# ringled.net
KiCad netlist of a schematic drawn in Altium Designer
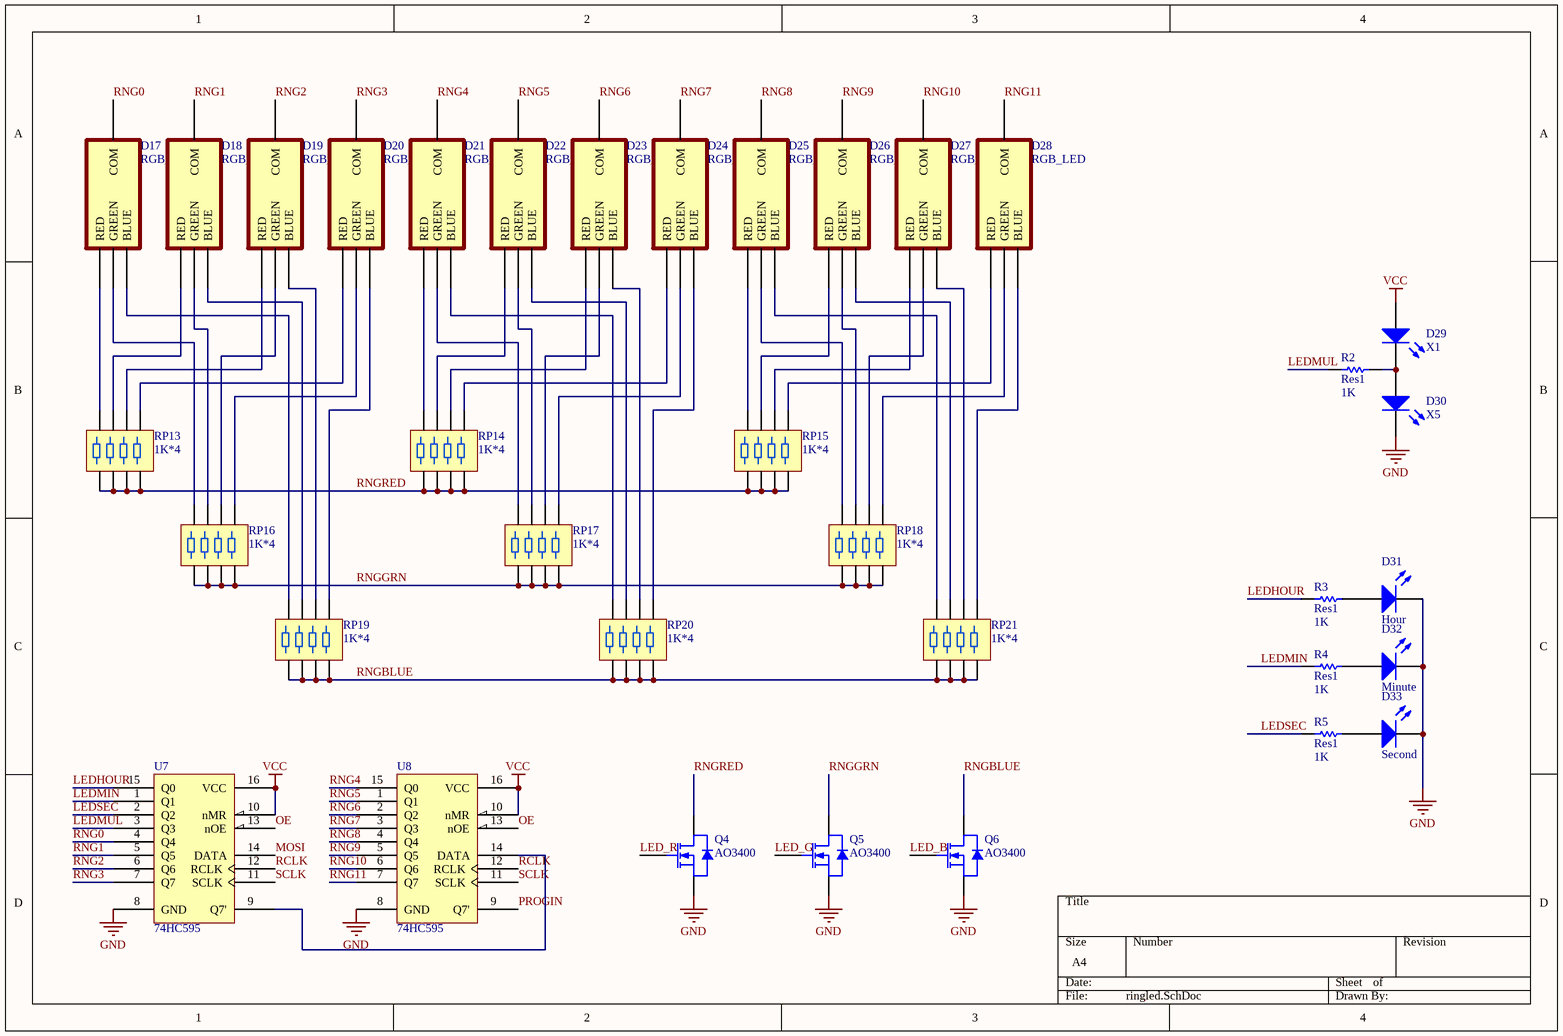
[diagram p0: ringled.SchDoc]

(export (version "E")
  (design (tool "Eeschema 10.0.6"))
  (components
    (comp (ref "D17")
      (value "RGB_LED")
      (footprint "0805_RGB")
      (libsource (lib "ntw_oldschlib") (part "RGBLED"))
    )
    (comp (ref "D18")
      (value "RGB_LED")
      (footprint "0805_RGB")
      (libsource (lib "ntw_oldschlib") (part "RGBLED"))
    )
    (comp (ref "D19")
      (value "RGB_LED")
      (footprint "0805_RGB")
      (libsource (lib "ntw_oldschlib") (part "RGBLED"))
    )
    (comp (ref "D20")
      (value "RGB_LED")
      (footprint "0805_RGB")
      (libsource (lib "ntw_oldschlib") (part "RGBLED"))
    )
    (comp (ref "D21")
      (value "RGB_LED")
      (footprint "0805_RGB")
      (libsource (lib "ntw_oldschlib") (part "RGBLED"))
    )
    (comp (ref "D22")
      (value "RGB_LED")
      (footprint "0805_RGB")
      (libsource (lib "ntw_oldschlib") (part "RGBLED"))
    )
    (comp (ref "D23")
      (value "RGB_LED")
      (footprint "0805_RGB")
      (libsource (lib "ntw_oldschlib") (part "RGBLED"))
    )
    (comp (ref "D24")
      (value "RGB_LED")
      (footprint "0805_RGB")
      (libsource (lib "ntw_oldschlib") (part "RGBLED"))
    )
    (comp (ref "D25")
      (value "RGB_LED")
      (footprint "0805_RGB")
      (libsource (lib "ntw_oldschlib") (part "RGBLED"))
    )
    (comp (ref "D26")
      (value "RGB_LED")
      (footprint "0805_RGB")
      (libsource (lib "ntw_oldschlib") (part "RGBLED"))
    )
    (comp (ref "D27")
      (value "RGB_LED")
      (footprint "0805_RGB")
      (libsource (lib "ntw_oldschlib") (part "RGBLED"))
    )
    (comp (ref "D28")
      (value "RGB_LED")
      (footprint "0805_RGB")
      (libsource (lib "ntw_oldschlib") (part "RGBLED"))
    )
    (comp (ref "D29")
      (value "X1")
      (footprint "0805_LED")
      (description "Typical INFRARED GaAs LED")
      (fields (field (name "PUBLISHER") "Altium Limited"))
      (libsource (lib "Miscellaneous Devices") (part "LED0"))
    )
    (comp (ref "D30")
      (value "X5")
      (footprint "0805_LED")
      (description "Typical INFRARED GaAs LED")
      (fields (field (name "PUBLISHER") "Altium Limited"))
      (libsource (lib "Miscellaneous Devices") (part "LED0"))
    )
    (comp (ref "D31")
      (value "Hour")
      (footprint "0805_LED")
      (description "Typical INFRARED GaAs LED")
      (fields (field (name "PUBLISHER") "Altium Limited"))
      (libsource (lib "Miscellaneous Devices") (part "LED0"))
    )
    (comp (ref "D32")
      (value "Minute")
      (footprint "0805_LED")
      (description "Typical INFRARED GaAs LED")
      (fields (field (name "PUBLISHER") "Altium Limited"))
      (libsource (lib "Miscellaneous Devices") (part "LED0"))
    )
    (comp (ref "D33")
      (value "Second")
      (footprint "0805_LED")
      (description "Typical INFRARED GaAs LED")
      (fields (field (name "PUBLISHER") "Altium Limited"))
      (libsource (lib "Miscellaneous Devices") (part "LED0"))
    )
    (comp (ref "Q4")
      (value "AO3400")
      (footprint "SOT-23")
      (description "N-Channel MOSFET")
      (fields (field (name "PUBLISHER") "Altium Limited"))
      (libsource (lib "ntw_oldschlib") (part "AO3400"))
    )
    (comp (ref "Q5")
      (value "AO3400")
      (footprint "SOT-23")
      (description "N-Channel MOSFET")
      (fields (field (name "PUBLISHER") "Altium Limited"))
      (libsource (lib "ntw_oldschlib") (part "AO3400"))
    )
    (comp (ref "Q6")
      (value "AO3400")
      (footprint "SOT-23")
      (description "N-Channel MOSFET")
      (fields (field (name "PUBLISHER") "Altium Limited"))
      (libsource (lib "ntw_oldschlib") (part "AO3400"))
    )
    (comp (ref "R2")
      (value "Res1")
      (footprint "0805")
      (description "Resistor")
      (fields (field (name "ALTIUM_VALUE") "1K") (field (name "PUBLISHER") "Altium Limited"))
      (libsource (lib "Miscellaneous Devices") (part "Res1"))
    )
    (comp (ref "R3")
      (value "Res1")
      (footprint "0805")
      (description "Resistor")
      (fields (field (name "ALTIUM_VALUE") "1K") (field (name "PUBLISHER") "Altium Limited"))
      (libsource (lib "Miscellaneous Devices") (part "Res1"))
    )
    (comp (ref "R4")
      (value "Res1")
      (footprint "0805")
      (description "Resistor")
      (fields (field (name "ALTIUM_VALUE") "1K") (field (name "PUBLISHER") "Altium Limited"))
      (libsource (lib "Miscellaneous Devices") (part "Res1"))
    )
    (comp (ref "R5")
      (value "Res1")
      (footprint "0805")
      (description "Resistor")
      (fields (field (name "ALTIUM_VALUE") "1K") (field (name "PUBLISHER") "Altium Limited"))
      (libsource (lib "Miscellaneous Devices") (part "Res1"))
    )
    (comp (ref "RP13") (value "1K*4") (footprint "0603X4") (libsource (lib "ntw_oldschlib") (part "RPack_4")))
    (comp (ref "RP14") (value "1K*4") (footprint "0603X4") (libsource (lib "ntw_oldschlib") (part "RPack_4")))
    (comp (ref "RP15") (value "1K*4") (footprint "0603X4") (libsource (lib "ntw_oldschlib") (part "RPack_4")))
    (comp (ref "RP16") (value "1K*4") (footprint "0603X4") (libsource (lib "ntw_oldschlib") (part "RPack_4")))
    (comp (ref "RP17") (value "1K*4") (footprint "0603X4") (libsource (lib "ntw_oldschlib") (part "RPack_4")))
    (comp (ref "RP18") (value "1K*4") (footprint "0603X4") (libsource (lib "ntw_oldschlib") (part "RPack_4")))
    (comp (ref "RP19") (value "1K*4") (footprint "0603X4") (libsource (lib "ntw_oldschlib") (part "RPack_4")))
    (comp (ref "RP20") (value "1K*4") (footprint "0603X4") (libsource (lib "ntw_oldschlib") (part "RPack_4")))
    (comp (ref "RP21") (value "1K*4") (footprint "0603X4") (libsource (lib "ntw_oldschlib") (part "RPack_4")))
    (comp (ref "U7")
      (value "74HC595")
      (footprint "TSSOP16")
      (description "8-bit serial-in, serial or parallel-out shift register with output latches; 3-state")
      (libsource (lib "ntw_oldschlib") (part "74HC595"))
    )
    (comp (ref "U8")
      (value "74HC595")
      (footprint "TSSOP16")
      (description "8-bit serial-in, serial or parallel-out shift register with output latches; 3-state")
      (libsource (lib "ntw_oldschlib") (part "74HC595"))
    )
  )
  (nets
    (net (code "1") (name "/LEDHOUR") (class "Default")
      (node (ref "R3") (pin "1") (pinfunction "1_1") (pintype "passive"))
      (node (ref "U7") (pin "15") (pinfunction "Q0_15") (pintype "passive"))
    )
    (net (code "2") (name "/LEDMIN") (class "Default")
      (node (ref "R4") (pin "1") (pinfunction "1_1") (pintype "passive"))
      (node (ref "U7") (pin "1") (pinfunction "Q1_1") (pintype "passive"))
    )
    (net (code "3") (name "/LEDMUL") (class "Default")
      (node (ref "R2") (pin "1") (pinfunction "1_1") (pintype "passive"))
      (node (ref "U7") (pin "3") (pinfunction "Q3_3") (pintype "passive"))
    )
    (net (code "4") (name "/LEDSEC") (class "Default")
      (node (ref "R5") (pin "1") (pinfunction "1_1") (pintype "passive"))
      (node (ref "U7") (pin "2") (pinfunction "Q2_2") (pintype "passive"))
    )
    (net (code "5") (name "/LED_B") (class "Default")
      (node (ref "Q6") (pin "1") (pinfunction "G_1") (pintype "passive"))
    )
    (net (code "6") (name "/LED_G") (class "Default")
      (node (ref "Q5") (pin "1") (pinfunction "G_1") (pintype "passive"))
    )
    (net (code "7") (name "/LED_R") (class "Default")
      (node (ref "Q4") (pin "1") (pinfunction "G_1") (pintype "passive"))
    )
    (net (code "8") (name "/MOSI") (class "Default")
      (node (ref "U7") (pin "14") (pinfunction "DATA_14") (pintype "passive"))
    )
    (net (code "9") (name "/OE") (class "Default")
      (node (ref "U7") (pin "13") (pinfunction "nOE_13") (pintype "passive"))
      (node (ref "U8") (pin "13") (pinfunction "nOE_13") (pintype "passive"))
    )
    (net (code "10") (name "/PROGIN") (class "Default")
      (node (ref "U8") (pin "9") (pinfunction "Q7'_9") (pintype "passive"))
    )
    (net (code "11") (name "/RCLK") (class "Default")
      (node (ref "U7") (pin "12") (pinfunction "RCLK_12") (pintype "passive"))
      (node (ref "U8") (pin "12") (pinfunction "RCLK_12") (pintype "passive"))
    )
    (net (code "12") (name "/RNG0") (class "Default")
      (node (ref "D17") (pin "COM") (pinfunction "COM_COM") (pintype "passive"))
      (node (ref "U7") (pin "4") (pinfunction "Q4_4") (pintype "passive"))
    )
    (net (code "13") (name "/RNG1") (class "Default")
      (node (ref "D18") (pin "COM") (pinfunction "COM_COM") (pintype "passive"))
      (node (ref "U7") (pin "5") (pinfunction "Q5_5") (pintype "passive"))
    )
    (net (code "14") (name "/RNG2") (class "Default")
      (node (ref "D19") (pin "COM") (pinfunction "COM_COM") (pintype "passive"))
      (node (ref "U7") (pin "6") (pinfunction "Q6_6") (pintype "passive"))
    )
    (net (code "15") (name "/RNG3") (class "Default")
      (node (ref "D20") (pin "COM") (pinfunction "COM_COM") (pintype "passive"))
      (node (ref "U7") (pin "7") (pinfunction "Q7_7") (pintype "passive"))
    )
    (net (code "16") (name "/RNG4") (class "Default")
      (node (ref "D21") (pin "COM") (pinfunction "COM_COM") (pintype "passive"))
      (node (ref "U8") (pin "15") (pinfunction "Q0_15") (pintype "passive"))
    )
    (net (code "17") (name "/RNG5") (class "Default")
      (node (ref "D22") (pin "COM") (pinfunction "COM_COM") (pintype "passive"))
      (node (ref "U8") (pin "1") (pinfunction "Q1_1") (pintype "passive"))
    )
    (net (code "18") (name "/RNG6") (class "Default")
      (node (ref "D23") (pin "COM") (pinfunction "COM_COM") (pintype "passive"))
      (node (ref "U8") (pin "2") (pinfunction "Q2_2") (pintype "passive"))
    )
    (net (code "19") (name "/RNG7") (class "Default")
      (node (ref "D24") (pin "COM") (pinfunction "COM_COM") (pintype "passive"))
      (node (ref "U8") (pin "3") (pinfunction "Q3_3") (pintype "passive"))
    )
    (net (code "20") (name "/RNG8") (class "Default")
      (node (ref "D25") (pin "COM") (pinfunction "COM_COM") (pintype "passive"))
      (node (ref "U8") (pin "4") (pinfunction "Q4_4") (pintype "passive"))
    )
    (net (code "21") (name "/RNG9") (class "Default")
      (node (ref "D26") (pin "COM") (pinfunction "COM_COM") (pintype "passive"))
      (node (ref "U8") (pin "5") (pinfunction "Q5_5") (pintype "passive"))
    )
    (net (code "22") (name "/RNG10") (class "Default")
      (node (ref "D27") (pin "COM") (pinfunction "COM_COM") (pintype "passive"))
      (node (ref "U8") (pin "6") (pinfunction "Q6_6") (pintype "passive"))
    )
    (net (code "23") (name "/RNG11") (class "Default")
      (node (ref "D28") (pin "COM") (pinfunction "COM_COM") (pintype "passive"))
      (node (ref "U8") (pin "7") (pinfunction "Q7_7") (pintype "passive"))
    )
    (net (code "24") (name "/RNGBLUE") (class "Default")
      (node (ref "Q6") (pin "3") (pinfunction "D_3") (pintype "passive"))
      (node (ref "RP19") (pin "1") (pinfunction "1_1") (pintype "passive"))
      (node (ref "RP19") (pin "2") (pinfunction "2_2") (pintype "passive"))
      (node (ref "RP19") (pin "3") (pinfunction "3_3") (pintype "passive"))
      (node (ref "RP19") (pin "4") (pinfunction "4_4") (pintype "passive"))
      (node (ref "RP20") (pin "1") (pinfunction "1_1") (pintype "passive"))
      (node (ref "RP20") (pin "2") (pinfunction "2_2") (pintype "passive"))
      (node (ref "RP20") (pin "3") (pinfunction "3_3") (pintype "passive"))
      (node (ref "RP20") (pin "4") (pinfunction "4_4") (pintype "passive"))
      (node (ref "RP21") (pin "1") (pinfunction "1_1") (pintype "passive"))
      (node (ref "RP21") (pin "2") (pinfunction "2_2") (pintype "passive"))
      (node (ref "RP21") (pin "3") (pinfunction "3_3") (pintype "passive"))
      (node (ref "RP21") (pin "4") (pinfunction "4_4") (pintype "passive"))
    )
    (net (code "25") (name "/RNGGRN") (class "Default")
      (node (ref "Q5") (pin "3") (pinfunction "D_3") (pintype "passive"))
      (node (ref "RP16") (pin "1") (pinfunction "1_1") (pintype "passive"))
      (node (ref "RP16") (pin "2") (pinfunction "2_2") (pintype "passive"))
      (node (ref "RP16") (pin "3") (pinfunction "3_3") (pintype "passive"))
      (node (ref "RP16") (pin "4") (pinfunction "4_4") (pintype "passive"))
      (node (ref "RP17") (pin "1") (pinfunction "1_1") (pintype "passive"))
      (node (ref "RP17") (pin "2") (pinfunction "2_2") (pintype "passive"))
      (node (ref "RP17") (pin "3") (pinfunction "3_3") (pintype "passive"))
      (node (ref "RP17") (pin "4") (pinfunction "4_4") (pintype "passive"))
      (node (ref "RP18") (pin "1") (pinfunction "1_1") (pintype "passive"))
      (node (ref "RP18") (pin "2") (pinfunction "2_2") (pintype "passive"))
      (node (ref "RP18") (pin "3") (pinfunction "3_3") (pintype "passive"))
      (node (ref "RP18") (pin "4") (pinfunction "4_4") (pintype "passive"))
    )
    (net (code "26") (name "/RNGRED") (class "Default")
      (node (ref "Q4") (pin "3") (pinfunction "D_3") (pintype "passive"))
      (node (ref "RP13") (pin "1") (pinfunction "1_1") (pintype "passive"))
      (node (ref "RP13") (pin "2") (pinfunction "2_2") (pintype "passive"))
      (node (ref "RP13") (pin "3") (pinfunction "3_3") (pintype "passive"))
      (node (ref "RP13") (pin "4") (pinfunction "4_4") (pintype "passive"))
      (node (ref "RP14") (pin "1") (pinfunction "1_1") (pintype "passive"))
      (node (ref "RP14") (pin "2") (pinfunction "2_2") (pintype "passive"))
      (node (ref "RP14") (pin "3") (pinfunction "3_3") (pintype "passive"))
      (node (ref "RP14") (pin "4") (pinfunction "4_4") (pintype "passive"))
      (node (ref "RP15") (pin "1") (pinfunction "1_1") (pintype "passive"))
      (node (ref "RP15") (pin "2") (pinfunction "2_2") (pintype "passive"))
      (node (ref "RP15") (pin "3") (pinfunction "3_3") (pintype "passive"))
      (node (ref "RP15") (pin "4") (pinfunction "4_4") (pintype "passive"))
    )
    (net (code "27") (name "/SCLK") (class "Default")
      (node (ref "U7") (pin "11") (pinfunction "SCLK_11") (pintype "passive"))
      (node (ref "U8") (pin "11") (pinfunction "SCLK_11") (pintype "passive"))
    )
    (net (code "28") (name "GND") (class "Default")
      (node (ref "D30") (pin "2") (pinfunction "K_2") (pintype "passive"))
      (node (ref "D31") (pin "2") (pinfunction "K_2") (pintype "passive"))
      (node (ref "D32") (pin "2") (pinfunction "K_2") (pintype "passive"))
      (node (ref "D33") (pin "2") (pinfunction "K_2") (pintype "passive"))
      (node (ref "Q4") (pin "2") (pinfunction "S_2") (pintype "passive"))
      (node (ref "Q5") (pin "2") (pinfunction "S_2") (pintype "passive"))
      (node (ref "Q6") (pin "2") (pinfunction "S_2") (pintype "passive"))
      (node (ref "U7") (pin "8") (pinfunction "GND_8") (pintype "passive"))
      (node (ref "U8") (pin "8") (pinfunction "GND_8") (pintype "passive"))
    )
    (net (code "29") (name "Net-(D17-BLUE)") (class "Default")
      (node (ref "D17") (pin "B") (pinfunction "BLUE_B") (pintype "passive"))
      (node (ref "RP19") (pin "8") (pinfunction "8_8") (pintype "passive"))
    )
    (net (code "30") (name "Net-(D17-GREEN)") (class "Default")
      (node (ref "D17") (pin "G") (pinfunction "GREEN_G") (pintype "passive"))
      (node (ref "RP16") (pin "8") (pinfunction "8_8") (pintype "passive"))
    )
    (net (code "31") (name "Net-(D17-RED)") (class "Default")
      (node (ref "D17") (pin "R") (pinfunction "RED_R") (pintype "passive"))
      (node (ref "RP13") (pin "8") (pinfunction "8_8") (pintype "passive"))
    )
    (net (code "32") (name "Net-(D18-BLUE)") (class "Default")
      (node (ref "D18") (pin "B") (pinfunction "BLUE_B") (pintype "passive"))
      (node (ref "RP19") (pin "7") (pinfunction "7_7") (pintype "passive"))
    )
    (net (code "33") (name "Net-(D18-GREEN)") (class "Default")
      (node (ref "D18") (pin "G") (pinfunction "GREEN_G") (pintype "passive"))
      (node (ref "RP16") (pin "7") (pinfunction "7_7") (pintype "passive"))
    )
    (net (code "34") (name "Net-(D18-RED)") (class "Default")
      (node (ref "D18") (pin "R") (pinfunction "RED_R") (pintype "passive"))
      (node (ref "RP13") (pin "7") (pinfunction "7_7") (pintype "passive"))
    )
    (net (code "35") (name "Net-(D19-BLUE)") (class "Default")
      (node (ref "D19") (pin "B") (pinfunction "BLUE_B") (pintype "passive"))
      (node (ref "RP19") (pin "6") (pinfunction "6_6") (pintype "passive"))
    )
    (net (code "36") (name "Net-(D19-GREEN)") (class "Default")
      (node (ref "D19") (pin "G") (pinfunction "GREEN_G") (pintype "passive"))
      (node (ref "RP16") (pin "6") (pinfunction "6_6") (pintype "passive"))
    )
    (net (code "37") (name "Net-(D19-RED)") (class "Default")
      (node (ref "D19") (pin "R") (pinfunction "RED_R") (pintype "passive"))
      (node (ref "RP13") (pin "6") (pinfunction "6_6") (pintype "passive"))
    )
    (net (code "38") (name "Net-(D20-BLUE)") (class "Default")
      (node (ref "D20") (pin "B") (pinfunction "BLUE_B") (pintype "passive"))
      (node (ref "RP19") (pin "5") (pinfunction "5_5") (pintype "passive"))
    )
    (net (code "39") (name "Net-(D20-GREEN)") (class "Default")
      (node (ref "D20") (pin "G") (pinfunction "GREEN_G") (pintype "passive"))
      (node (ref "RP16") (pin "5") (pinfunction "5_5") (pintype "passive"))
    )
    (net (code "40") (name "Net-(D20-RED)") (class "Default")
      (node (ref "D20") (pin "R") (pinfunction "RED_R") (pintype "passive"))
      (node (ref "RP13") (pin "5") (pinfunction "5_5") (pintype "passive"))
    )
    (net (code "41") (name "Net-(D21-BLUE)") (class "Default")
      (node (ref "D21") (pin "B") (pinfunction "BLUE_B") (pintype "passive"))
      (node (ref "RP20") (pin "8") (pinfunction "8_8") (pintype "passive"))
    )
    (net (code "42") (name "Net-(D21-GREEN)") (class "Default")
      (node (ref "D21") (pin "G") (pinfunction "GREEN_G") (pintype "passive"))
      (node (ref "RP17") (pin "8") (pinfunction "8_8") (pintype "passive"))
    )
    (net (code "43") (name "Net-(D21-RED)") (class "Default")
      (node (ref "D21") (pin "R") (pinfunction "RED_R") (pintype "passive"))
      (node (ref "RP14") (pin "8") (pinfunction "8_8") (pintype "passive"))
    )
    (net (code "44") (name "Net-(D22-BLUE)") (class "Default")
      (node (ref "D22") (pin "B") (pinfunction "BLUE_B") (pintype "passive"))
      (node (ref "RP20") (pin "7") (pinfunction "7_7") (pintype "passive"))
    )
    (net (code "45") (name "Net-(D22-GREEN)") (class "Default")
      (node (ref "D22") (pin "G") (pinfunction "GREEN_G") (pintype "passive"))
      (node (ref "RP17") (pin "7") (pinfunction "7_7") (pintype "passive"))
    )
    (net (code "46") (name "Net-(D22-RED)") (class "Default")
      (node (ref "D22") (pin "R") (pinfunction "RED_R") (pintype "passive"))
      (node (ref "RP14") (pin "7") (pinfunction "7_7") (pintype "passive"))
    )
    (net (code "47") (name "Net-(D23-BLUE)") (class "Default")
      (node (ref "D23") (pin "B") (pinfunction "BLUE_B") (pintype "passive"))
      (node (ref "RP20") (pin "6") (pinfunction "6_6") (pintype "passive"))
    )
    (net (code "48") (name "Net-(D23-GREEN)") (class "Default")
      (node (ref "D23") (pin "G") (pinfunction "GREEN_G") (pintype "passive"))
      (node (ref "RP17") (pin "6") (pinfunction "6_6") (pintype "passive"))
    )
    (net (code "49") (name "Net-(D23-RED)") (class "Default")
      (node (ref "D23") (pin "R") (pinfunction "RED_R") (pintype "passive"))
      (node (ref "RP14") (pin "6") (pinfunction "6_6") (pintype "passive"))
    )
    (net (code "50") (name "Net-(D24-BLUE)") (class "Default")
      (node (ref "D24") (pin "B") (pinfunction "BLUE_B") (pintype "passive"))
      (node (ref "RP20") (pin "5") (pinfunction "5_5") (pintype "passive"))
    )
    (net (code "51") (name "Net-(D24-GREEN)") (class "Default")
      (node (ref "D24") (pin "G") (pinfunction "GREEN_G") (pintype "passive"))
      (node (ref "RP17") (pin "5") (pinfunction "5_5") (pintype "passive"))
    )
    (net (code "52") (name "Net-(D24-RED)") (class "Default")
      (node (ref "D24") (pin "R") (pinfunction "RED_R") (pintype "passive"))
      (node (ref "RP14") (pin "5") (pinfunction "5_5") (pintype "passive"))
    )
    (net (code "53") (name "Net-(D25-BLUE)") (class "Default")
      (node (ref "D25") (pin "B") (pinfunction "BLUE_B") (pintype "passive"))
      (node (ref "RP21") (pin "8") (pinfunction "8_8") (pintype "passive"))
    )
    (net (code "54") (name "Net-(D25-GREEN)") (class "Default")
      (node (ref "D25") (pin "G") (pinfunction "GREEN_G") (pintype "passive"))
      (node (ref "RP18") (pin "8") (pinfunction "8_8") (pintype "passive"))
    )
    (net (code "55") (name "Net-(D25-RED)") (class "Default")
      (node (ref "D25") (pin "R") (pinfunction "RED_R") (pintype "passive"))
      (node (ref "RP15") (pin "8") (pinfunction "8_8") (pintype "passive"))
    )
    (net (code "56") (name "Net-(D26-BLUE)") (class "Default")
      (node (ref "D26") (pin "B") (pinfunction "BLUE_B") (pintype "passive"))
      (node (ref "RP21") (pin "7") (pinfunction "7_7") (pintype "passive"))
    )
    (net (code "57") (name "Net-(D26-GREEN)") (class "Default")
      (node (ref "D26") (pin "G") (pinfunction "GREEN_G") (pintype "passive"))
      (node (ref "RP18") (pin "7") (pinfunction "7_7") (pintype "passive"))
    )
    (net (code "58") (name "Net-(D26-RED)") (class "Default")
      (node (ref "D26") (pin "R") (pinfunction "RED_R") (pintype "passive"))
      (node (ref "RP15") (pin "7") (pinfunction "7_7") (pintype "passive"))
    )
    (net (code "59") (name "Net-(D27-BLUE)") (class "Default")
      (node (ref "D27") (pin "B") (pinfunction "BLUE_B") (pintype "passive"))
      (node (ref "RP21") (pin "6") (pinfunction "6_6") (pintype "passive"))
    )
    (net (code "60") (name "Net-(D27-GREEN)") (class "Default")
      (node (ref "D27") (pin "G") (pinfunction "GREEN_G") (pintype "passive"))
      (node (ref "RP18") (pin "6") (pinfunction "6_6") (pintype "passive"))
    )
    (net (code "61") (name "Net-(D27-RED)") (class "Default")
      (node (ref "D27") (pin "R") (pinfunction "RED_R") (pintype "passive"))
      (node (ref "RP15") (pin "6") (pinfunction "6_6") (pintype "passive"))
    )
    (net (code "62") (name "Net-(D28-BLUE)") (class "Default")
      (node (ref "D28") (pin "B") (pinfunction "BLUE_B") (pintype "passive"))
      (node (ref "RP21") (pin "5") (pinfunction "5_5") (pintype "passive"))
    )
    (net (code "63") (name "Net-(D28-GREEN)") (class "Default")
      (node (ref "D28") (pin "G") (pinfunction "GREEN_G") (pintype "passive"))
      (node (ref "RP18") (pin "5") (pinfunction "5_5") (pintype "passive"))
    )
    (net (code "64") (name "Net-(D28-RED)") (class "Default")
      (node (ref "D28") (pin "R") (pinfunction "RED_R") (pintype "passive"))
      (node (ref "RP15") (pin "5") (pinfunction "5_5") (pintype "passive"))
    )
    (net (code "65") (name "Net-(D29-K)") (class "Default")
      (node (ref "D29") (pin "2") (pinfunction "K_2") (pintype "passive"))
      (node (ref "D30") (pin "1") (pinfunction "A_1") (pintype "passive"))
      (node (ref "R2") (pin "2") (pinfunction "2_2") (pintype "passive"))
    )
    (net (code "66") (name "Net-(D31-A)") (class "Default")
      (node (ref "D31") (pin "1") (pinfunction "A_1") (pintype "passive"))
      (node (ref "R3") (pin "2") (pinfunction "2_2") (pintype "passive"))
    )
    (net (code "67") (name "Net-(D32-A)") (class "Default")
      (node (ref "D32") (pin "1") (pinfunction "A_1") (pintype "passive"))
      (node (ref "R4") (pin "2") (pinfunction "2_2") (pintype "passive"))
    )
    (net (code "68") (name "Net-(D33-A)") (class "Default")
      (node (ref "D33") (pin "1") (pinfunction "A_1") (pintype "passive"))
      (node (ref "R5") (pin "2") (pinfunction "2_2") (pintype "passive"))
    )
    (net (code "69") (name "Net-(U7-Q7')") (class "Default")
      (node (ref "U7") (pin "9") (pinfunction "Q7'_9") (pintype "passive"))
      (node (ref "U8") (pin "14") (pinfunction "DATA_14") (pintype "passive"))
    )
    (net (code "70") (name "VCC") (class "Default")
      (node (ref "D29") (pin "1") (pinfunction "A_1") (pintype "passive"))
      (node (ref "U7") (pin "10") (pinfunction "nMR_10") (pintype "passive"))
      (node (ref "U7") (pin "16") (pinfunction "VCC_16") (pintype "passive"))
      (node (ref "U8") (pin "10") (pinfunction "nMR_10") (pintype "passive"))
      (node (ref "U8") (pin "16") (pinfunction "VCC_16") (pintype "passive"))
    )
  )
)
